# 4_SFP.net
KiCad netlist of a schematic drawn in Altium Designer
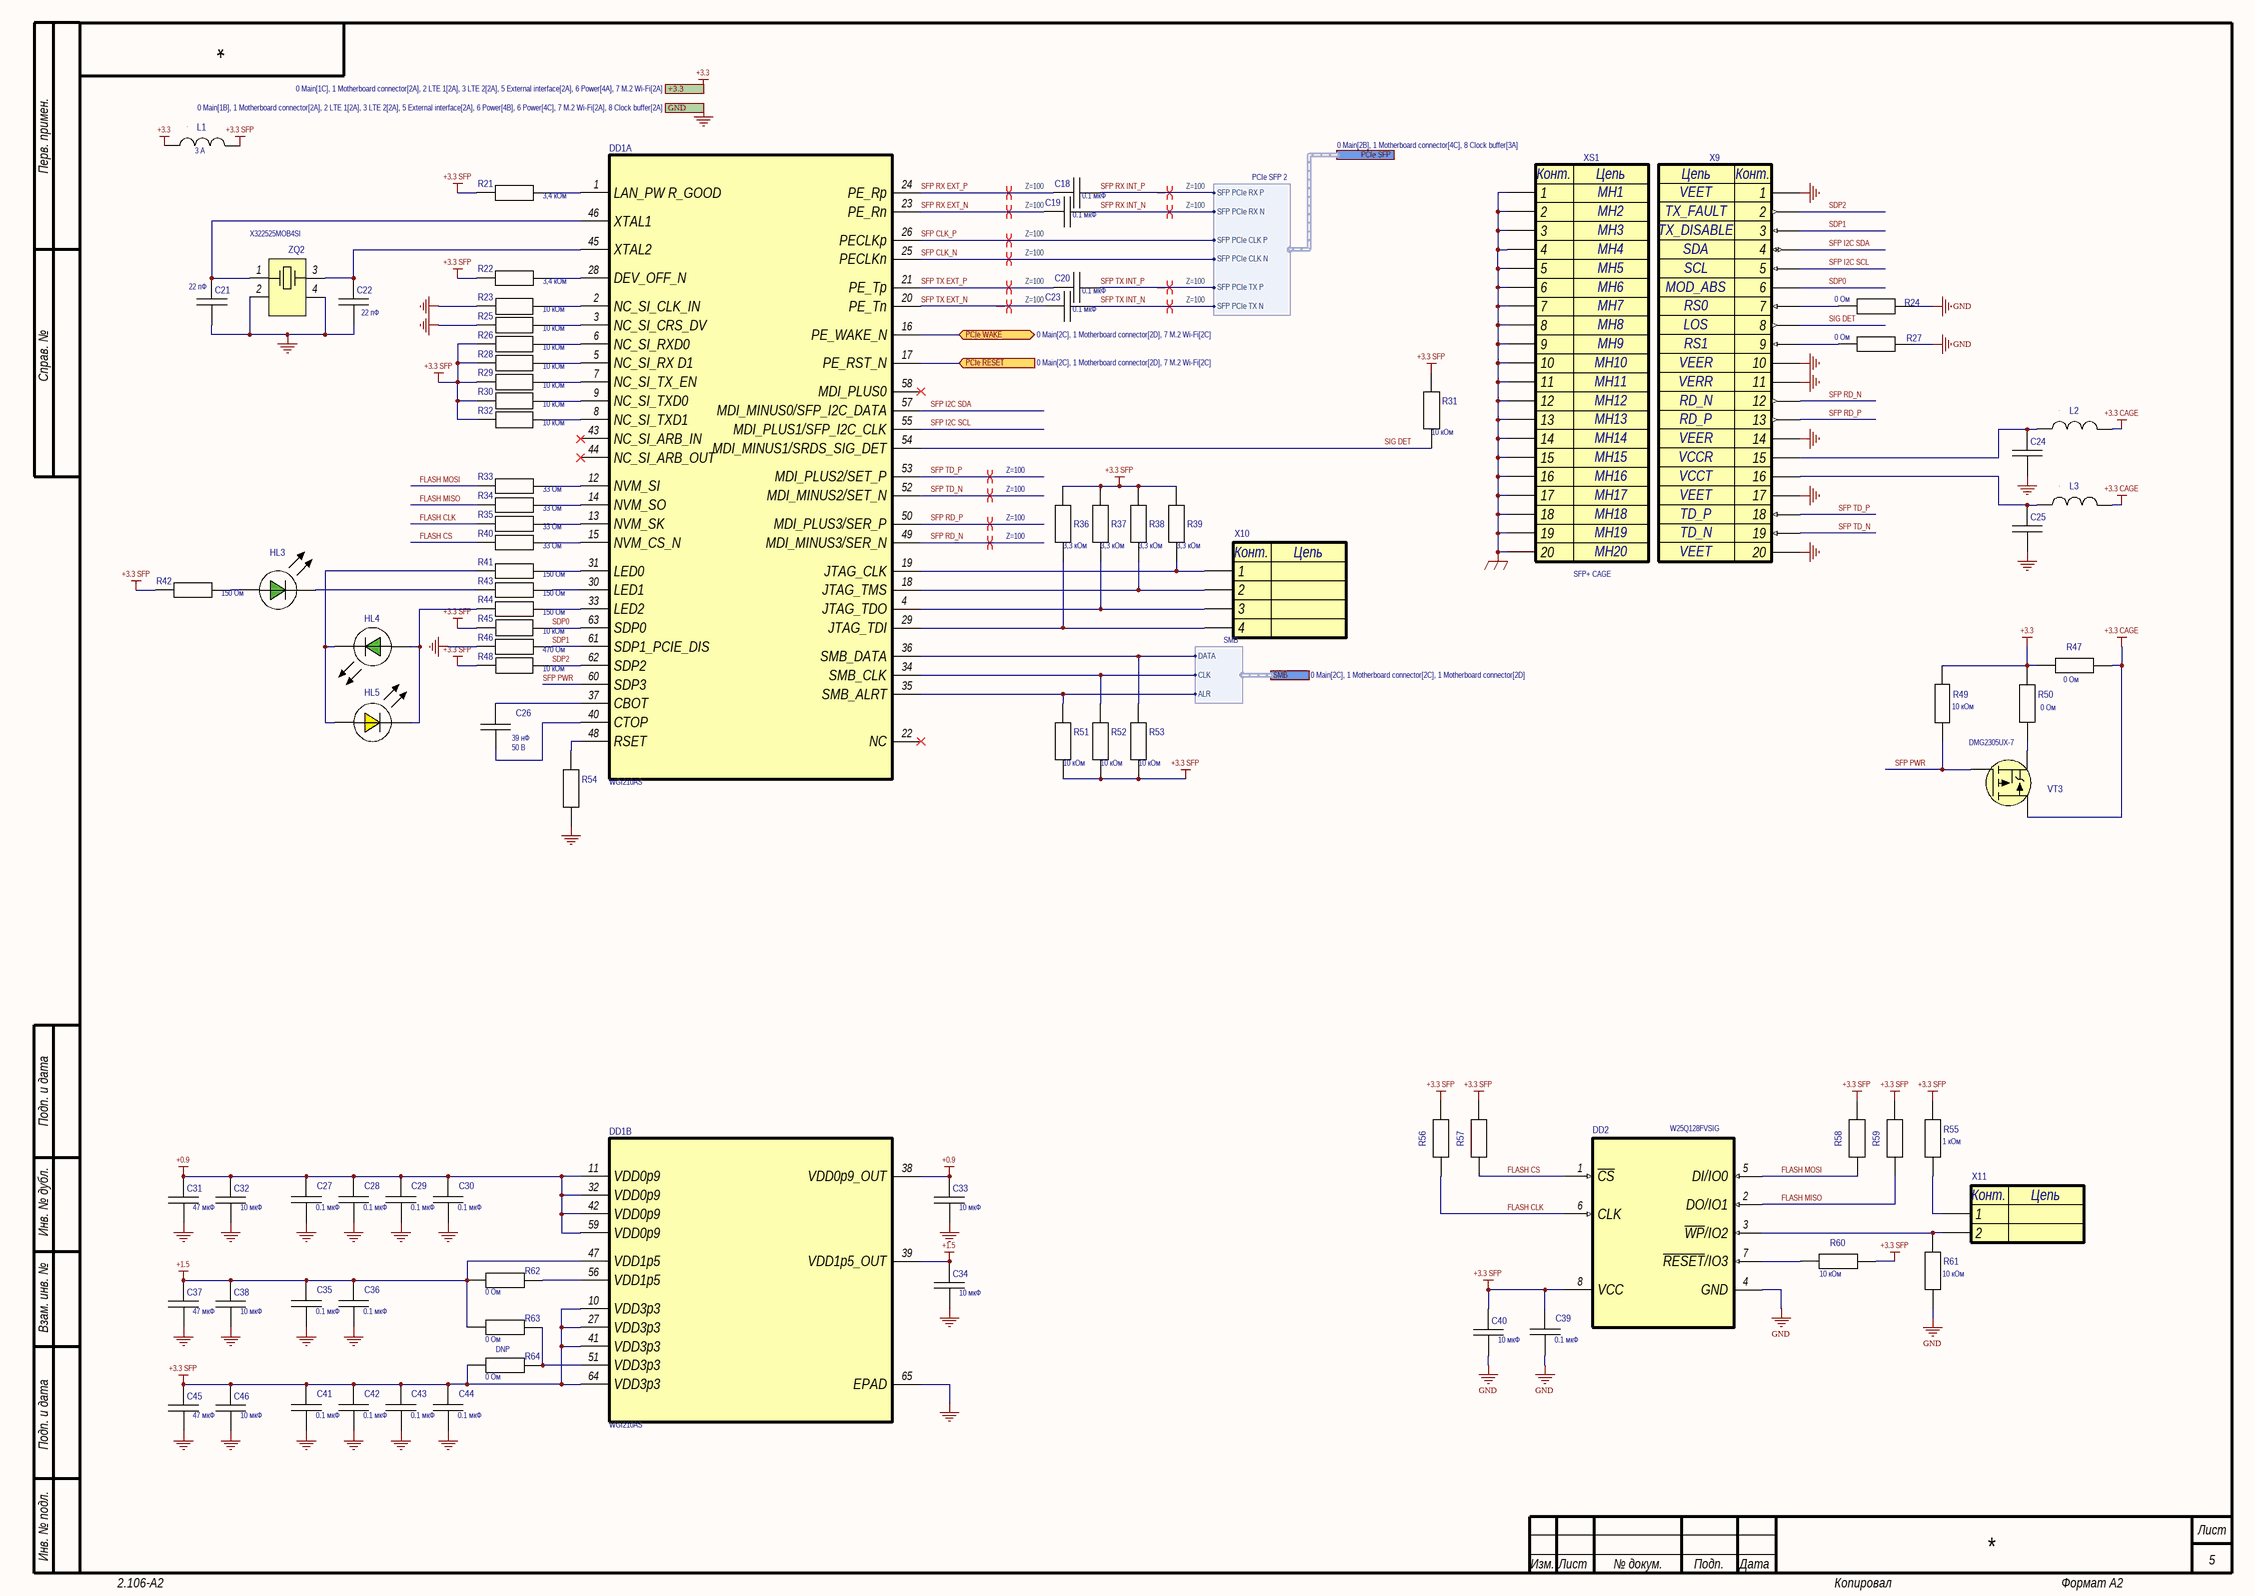
[diagram p0: 4 SFP.SchDoc]

(export (version "E")
  (design (tool "Eeschema 10.0.6"))
  (components
    (comp (ref "C18")
      (value "0.1 мкФ")
      (footprint "CAP_0402")
      (description "Конденсатор CHIP-0402 0.1 мкФ 50 В 10% X7R")
      (fields (field (name "PARTNUMBER") "CC0402KRX7R9BB104") (field (name "TOLERANCE") "10%"))
      (libsource (lib "Database_Altium") (part "STD_CAP"))
    )
    (comp (ref "C19")
      (value "0.1 мкФ")
      (footprint "CAP_0402")
      (description "Конденсатор CHIP-0402 0.1 мкФ 50 В 10% X7R")
      (fields (field (name "PARTNUMBER") "CC0402KRX7R9BB104") (field (name "TOLERANCE") "10%"))
      (libsource (lib "Database_Altium") (part "STD_CAP"))
    )
    (comp (ref "C20")
      (value "0.1 мкФ")
      (footprint "CAP_0402")
      (description "Конденсатор CHIP-0402 0.1 мкФ 50 В 10% X7R")
      (fields (field (name "PARTNUMBER") "CC0402KRX7R9BB104") (field (name "TOLERANCE") "10%"))
      (libsource (lib "Database_Altium") (part "STD_CAP"))
    )
    (comp (ref "C21")
      (value "22 пФ")
      (footprint "CAP_0402")
      (description "Конденсатор CHIP-0402 22 пФ 50 В 5% NPO")
      (fields (field (name "PARTNUMBER") "CC0402JRNPO9BN220") (field (name "TOLERANCE") "5%"))
      (libsource (lib "Database_Altium") (part "STD_CAP"))
    )
    (comp (ref "C22")
      (value "22 пФ")
      (footprint "CAP_0402")
      (description "Конденсатор CHIP-0402 22 пФ 50 В 5% NPO")
      (fields (field (name "PARTNUMBER") "CC0402JRNPO9BN220") (field (name "TOLERANCE") "5%"))
      (libsource (lib "Database_Altium") (part "STD_CAP"))
    )
    (comp (ref "C23")
      (value "0.1 мкФ")
      (footprint "CAP_0402")
      (description "Конденсатор CHIP-0402 0.1 мкФ 50 В 10% X7R")
      (fields (field (name "PARTNUMBER") "CC0402KRX7R9BB104") (field (name "TOLERANCE") "10%"))
      (libsource (lib "Database_Altium") (part "STD_CAP"))
    )
    (comp (ref "C24")
      (value "~")
      (footprint "CAP_0805")
      (description "Конденсатор CHIP-0805 4.7 мкФ 10 В 10% X7R")
      (fields (field (name "PARTNUMBER") "CC0805KKX7R6BB475") (field (name "TOLERANCE") "10%"))
      (libsource (lib "Database_Altium") (part "STD_CAP"))
    )
    (comp (ref "C25")
      (value "~")
      (footprint "CAP_0805")
      (description "Конденсатор CHIP-0805 4.7 мкФ 10 В 10% X7R")
      (fields (field (name "PARTNUMBER") "CC0805KKX7R6BB475") (field (name "TOLERANCE") "10%"))
      (libsource (lib "Database_Altium") (part "STD_CAP"))
    )
    (comp (ref "C26")
      (value "39 нФ")
      (footprint "CAP_0603")
      (description "Конденсатор CHIP-0603 39 нФ 50 В 10% X7R")
      (fields
        (field (name "PARTNUMBER") "CC0603KRX7R9BB393")
        (field (name "TOLERANCE") "10%")
        (field (name "НАПРЯЖЕНИЕ") "50 В")
      )
      (libsource (lib "Database_Altium") (part "STD_CAP"))
    )
    (comp (ref "C27")
      (value "0.1 мкФ")
      (footprint "CAP_0402")
      (description "Конденсатор CHIP-0402 0.1 мкФ 50 В 10% X7R")
      (fields (field (name "PARTNUMBER") "CC0402KRX7R9BB104") (field (name "TOLERANCE") "10%"))
      (libsource (lib "Database_Altium") (part "STD_CAP"))
    )
    (comp (ref "C28")
      (value "0.1 мкФ")
      (footprint "CAP_0402")
      (description "Конденсатор CHIP-0402 0.1 мкФ 50 В 10% X7R")
      (fields (field (name "PARTNUMBER") "CC0402KRX7R9BB104") (field (name "TOLERANCE") "10%"))
      (libsource (lib "Database_Altium") (part "STD_CAP"))
    )
    (comp (ref "C29")
      (value "0.1 мкФ")
      (footprint "CAP_0402")
      (description "Конденсатор CHIP-0402 0.1 мкФ 50 В 10% X7R")
      (fields (field (name "PARTNUMBER") "CC0402KRX7R9BB104") (field (name "TOLERANCE") "10%"))
      (libsource (lib "Database_Altium") (part "STD_CAP"))
    )
    (comp (ref "C30")
      (value "0.1 мкФ")
      (footprint "CAP_0402")
      (description "Конденсатор CHIP-0402 0.1 мкФ 50 В 10% X7R")
      (fields (field (name "PARTNUMBER") "CC0402KRX7R9BB104") (field (name "TOLERANCE") "10%"))
      (libsource (lib "Database_Altium") (part "STD_CAP"))
    )
    (comp (ref "C31")
      (value "47 мкФ")
      (footprint "CAP_0805")
      (description "Конденсатор CHIP-0805 47 мкФ 6.3 В 20% X5R")
      (fields (field (name "PARTNUMBER") "GRM21BR60J476ME15L") (field (name "TOLERANCE") "20%"))
      (libsource (lib "Database_Altium") (part "STD_CAP"))
    )
    (comp (ref "C32")
      (value "10 мкФ")
      (footprint "CAP_0402_BIG")
      (description "Конденсатор CHIP-0402 10 мкФ 6.3 В 20% X5R")
      (fields (field (name "PARTNUMBER") "CC0402MRX5R5BB106") (field (name "TOLERANCE") "20%"))
      (libsource (lib "Database_Altium") (part "STD_CAP"))
    )
    (comp (ref "C33")
      (value "10 мкФ")
      (footprint "CAP_0402_BIG")
      (description "Конденсатор CHIP-0402 10 мкФ 6.3 В 20% X5R")
      (fields (field (name "PARTNUMBER") "CC0402MRX5R5BB106") (field (name "TOLERANCE") "20%"))
      (libsource (lib "Database_Altium") (part "STD_CAP"))
    )
    (comp (ref "C34")
      (value "10 мкФ")
      (footprint "CAP_0402_BIG")
      (description "Конденсатор CHIP-0402 10 мкФ 6.3 В 20% X5R")
      (fields (field (name "PARTNUMBER") "CC0402MRX5R5BB106") (field (name "TOLERANCE") "20%"))
      (libsource (lib "Database_Altium") (part "STD_CAP"))
    )
    (comp (ref "C35")
      (value "0.1 мкФ")
      (footprint "CAP_0402")
      (description "Конденсатор CHIP-0402 0.1 мкФ 50 В 10% X7R")
      (fields (field (name "PARTNUMBER") "CC0402KRX7R9BB104") (field (name "TOLERANCE") "10%"))
      (libsource (lib "Database_Altium") (part "STD_CAP"))
    )
    (comp (ref "C36")
      (value "0.1 мкФ")
      (footprint "CAP_0402")
      (description "Конденсатор CHIP-0402 0.1 мкФ 50 В 10% X7R")
      (fields (field (name "PARTNUMBER") "CC0402KRX7R9BB104") (field (name "TOLERANCE") "10%"))
      (libsource (lib "Database_Altium") (part "STD_CAP"))
    )
    (comp (ref "C37")
      (value "47 мкФ")
      (footprint "CAP_0805")
      (description "Конденсатор CHIP-0805 47 мкФ 6.3 В 20% X5R")
      (fields (field (name "PARTNUMBER") "GRM21BR60J476ME15L") (field (name "TOLERANCE") "20%"))
      (libsource (lib "Database_Altium") (part "STD_CAP"))
    )
    (comp (ref "C38")
      (value "10 мкФ")
      (footprint "CAP_0402_BIG")
      (description "Конденсатор CHIP-0402 10 мкФ 6.3 В 20% X5R")
      (fields (field (name "PARTNUMBER") "CC0402MRX5R5BB106") (field (name "TOLERANCE") "20%"))
      (libsource (lib "Database_Altium") (part "STD_CAP"))
    )
    (comp (ref "C39")
      (value "0.1 мкФ")
      (footprint "CAP_0402")
      (description "Конденсатор CHIP-0402 0.1 мкФ 50 В 10% X7R")
      (fields (field (name "PARTNUMBER") "CC0402KRX7R9BB104") (field (name "TOLERANCE") "10%"))
      (libsource (lib "Database_Altium") (part "STD_CAP"))
    )
    (comp (ref "C40")
      (value "10 мкФ")
      (footprint "CAP_0402_BIG")
      (description "Конденсатор CHIP-0402 10 мкФ 6.3 В 20% X5R")
      (fields (field (name "PARTNUMBER") "CC0402MRX5R5BB106") (field (name "TOLERANCE") "20%"))
      (libsource (lib "Database_Altium") (part "STD_CAP"))
    )
    (comp (ref "C41")
      (value "0.1 мкФ")
      (footprint "CAP_0402")
      (description "Конденсатор CHIP-0402 0.1 мкФ 50 В 10% X7R")
      (fields (field (name "PARTNUMBER") "CC0402KRX7R9BB104") (field (name "TOLERANCE") "10%"))
      (libsource (lib "Database_Altium") (part "STD_CAP"))
    )
    (comp (ref "C42")
      (value "0.1 мкФ")
      (footprint "CAP_0402")
      (description "Конденсатор CHIP-0402 0.1 мкФ 50 В 10% X7R")
      (fields (field (name "PARTNUMBER") "CC0402KRX7R9BB104") (field (name "TOLERANCE") "10%"))
      (libsource (lib "Database_Altium") (part "STD_CAP"))
    )
    (comp (ref "C43")
      (value "0.1 мкФ")
      (footprint "CAP_0402")
      (description "Конденсатор CHIP-0402 0.1 мкФ 50 В 10% X7R")
      (fields (field (name "PARTNUMBER") "CC0402KRX7R9BB104") (field (name "TOLERANCE") "10%"))
      (libsource (lib "Database_Altium") (part "STD_CAP"))
    )
    (comp (ref "C44")
      (value "0.1 мкФ")
      (footprint "CAP_0402")
      (description "Конденсатор CHIP-0402 0.1 мкФ 50 В 10% X7R")
      (fields (field (name "PARTNUMBER") "CC0402KRX7R9BB104") (field (name "TOLERANCE") "10%"))
      (libsource (lib "Database_Altium") (part "STD_CAP"))
    )
    (comp (ref "C45")
      (value "47 мкФ")
      (footprint "CAP_0805")
      (description "Конденсатор CHIP-0805 47 мкФ 6.3 В 20% X5R")
      (fields (field (name "PARTNUMBER") "GRM21BR60J476ME15L") (field (name "TOLERANCE") "20%"))
      (libsource (lib "Database_Altium") (part "STD_CAP"))
    )
    (comp (ref "C46")
      (value "10 мкФ")
      (footprint "CAP_0402_BIG")
      (description "Конденсатор CHIP-0402 10 мкФ 6.3 В 20% X5R")
      (fields (field (name "PARTNUMBER") "CC0402MRX5R5BB106") (field (name "TOLERANCE") "20%"))
      (libsource (lib "Database_Altium") (part "STD_CAP"))
    )
    (comp (ref "DD1")
      (value "WGI210AS")
      (footprint "QFN64-9X9-P05_WGI210AS")
      (description "Микросхема Intel  Ethernet Controller  PCIe v2.1 (2.5 GT/s) x1")
      (fields (field (name "VOLTAGE") "3.3 В") (field (name "MANUFACTURER") "Intel"))
      (libsource (lib "Database_Altium") (part "WGI210AS"))
    )
    (comp (ref "DD2")
      (value "W25Q128FVSIG")
      (footprint "SOIC-8-208mil")
      (description "Микросхема Winbond  3V 128M-BIT\r\nSERIAL FLASH MEMORY WITH\r\nDUAL/QUAD SPI & QPI")
      (fields
        (field (name "PARTNUMBER") "W25Q128FVSIG")
        (field (name "VOLTAGE") "2.7-3.3В")
        (field (name "MANUFACTURER") "Winbond")
      )
      (libsource (lib "Database_Altium") (part "W25Q128FVSIG"))
    )
    (comp (ref "HL3")
      (value "155124GS73200")
      (footprint "LED_1204_GREEN")
      (description "Диод Wurth 2 В 25 мА")
      (fields (field (name "MANUFACTURER") "Wurth"))
      (libsource (lib "Database_Altium") (part "STD_LED_GREEN"))
    )
    (comp (ref "HL4")
      (value "155124GS73200")
      (footprint "LED_1204_GREEN")
      (description "Диод Wurth 2 В 25 мА")
      (fields (field (name "MANUFACTURER") "Wurth"))
      (libsource (lib "Database_Altium") (part "STD_LED_GREEN"))
    )
    (comp (ref "HL5")
      (value "155124YS73200")
      (footprint "LED_1204_YELLOW")
      (description "Диод Wurth 2 В 25 мА")
      (fields (field (name "MANUFACTURER") "Wurth"))
      (libsource (lib "Database_Altium") (part "STD_LED_YELLOW"))
    )
    (comp (ref "L1")
      (value "STD_IND")
      (footprint "IND_0603")
      (description "Катушка индуктивности BEAD-0603 33 Ом @100 МГц 25%")
      (fields
        (field (name "PARTNUMBER") "BLM18PG330SN1D")
        (field (name "TOLERANCE") "25%")
        (field (name "CURRENT") "3 А")
      )
      (libsource (lib "Database_Altium") (part "STD_IND"))
    )
    (comp (ref "L2")
      (value "STD_IND")
      (footprint "IND_0603")
      (description "Катушка индуктивности CHIP-0603 3.3 мкГн 10%")
      (fields (field (name "PARTNUMBER") "MLF1608A3R3KTA00") (field (name "TOLERANCE") "10%"))
      (libsource (lib "Database_Altium") (part "STD_IND"))
    )
    (comp (ref "L3")
      (value "STD_IND")
      (footprint "IND_0603")
      (description "Катушка индуктивности CHIP-0603 3.3 мкГн 10%")
      (fields (field (name "PARTNUMBER") "MLF1608A3R3KTA00") (field (name "TOLERANCE") "10%"))
      (libsource (lib "Database_Altium") (part "STD_IND"))
    )
    (comp (ref "R21")
      (value "3,4 кОм")
      (footprint "RES_0402")
      (description "Резистор CHIP-0402 3,4 кОм 1%")
      (fields (field (name "PARTNUMBER") "RC0402FR-073K4L") (field (name "TOLERANCE") "1%"))
      (libsource (lib "Database_Altium") (part "STD_RES"))
    )
    (comp (ref "R22")
      (value "3,4 кОм")
      (footprint "RES_0402")
      (description "Резистор CHIP-0402 3,4 кОм 1%")
      (fields (field (name "PARTNUMBER") "RC0402FR-073K4L") (field (name "TOLERANCE") "1%"))
      (libsource (lib "Database_Altium") (part "STD_RES"))
    )
    (comp (ref "R23")
      (value "10 кОм")
      (footprint "RES_0402")
      (description "Резистор CHIP-0402 10 кОм 1%")
      (fields (field (name "PARTNUMBER") "RC0402FR-0710KL") (field (name "TOLERANCE") "1%"))
      (libsource (lib "Database_Altium") (part "STD_RES"))
    )
    (comp (ref "R24")
      (value "0 Ом")
      (footprint "RES_0402")
      (description "Резистор CHIP-0402 0 Ом 5%")
      (fields (field (name "PARTNUMBER") "RC0402JR-070RL") (field (name "TOLERANCE") "5%"))
      (libsource (lib "Database_Altium") (part "STD_RES"))
    )
    (comp (ref "R25")
      (value "10 кОм")
      (footprint "RES_0402")
      (description "Резистор CHIP-0402 10 кОм 1%")
      (fields (field (name "PARTNUMBER") "RC0402FR-0710KL") (field (name "TOLERANCE") "1%"))
      (libsource (lib "Database_Altium") (part "STD_RES"))
    )
    (comp (ref "R26")
      (value "10 кОм")
      (footprint "RES_0402")
      (description "Резистор CHIP-0402 10 кОм 1%")
      (fields (field (name "PARTNUMBER") "RC0402FR-0710KL") (field (name "TOLERANCE") "1%"))
      (libsource (lib "Database_Altium") (part "STD_RES"))
    )
    (comp (ref "R27")
      (value "0 Ом")
      (footprint "RES_0402")
      (description "Резистор CHIP-0402 0 Ом 5%")
      (fields (field (name "PARTNUMBER") "RC0402JR-070RL") (field (name "TOLERANCE") "5%"))
      (libsource (lib "Database_Altium") (part "STD_RES"))
    )
    (comp (ref "R28")
      (value "10 кОм")
      (footprint "RES_0402")
      (description "Резистор CHIP-0402 10 кОм 1%")
      (fields (field (name "PARTNUMBER") "RC0402FR-0710KL") (field (name "TOLERANCE") "1%"))
      (libsource (lib "Database_Altium") (part "STD_RES"))
    )
    (comp (ref "R29")
      (value "10 кОм")
      (footprint "RES_0402")
      (description "Резистор CHIP-0402 10 кОм 1%")
      (fields (field (name "PARTNUMBER") "RC0402FR-0710KL") (field (name "TOLERANCE") "1%"))
      (libsource (lib "Database_Altium") (part "STD_RES"))
    )
    (comp (ref "R30")
      (value "10 кОм")
      (footprint "RES_0402")
      (description "Резистор CHIP-0402 10 кОм 1%")
      (fields (field (name "PARTNUMBER") "RC0402FR-0710KL") (field (name "TOLERANCE") "1%"))
      (libsource (lib "Database_Altium") (part "STD_RES"))
    )
    (comp (ref "R31")
      (value "10 кОм")
      (footprint "RES_0402")
      (description "Резистор CHIP-0402 10 кОм 5%")
      (fields (field (name "PARTNUMBER") "RC0402JR-0710KL") (field (name "TOLERANCE") "5%"))
      (libsource (lib "Database_Altium") (part "STD_RES"))
    )
    (comp (ref "R32")
      (value "10 кОм")
      (footprint "RES_0402")
      (description "Резистор CHIP-0402 10 кОм 1%")
      (fields (field (name "PARTNUMBER") "RC0402FR-0710KL") (field (name "TOLERANCE") "1%"))
      (libsource (lib "Database_Altium") (part "STD_RES"))
    )
    (comp (ref "R33")
      (value "33 Ом")
      (footprint "RES_0402")
      (description "Резистор CHIP-0402 33 Ом 1%")
      (fields (field (name "PARTNUMBER") "RC0402FR-0733RL") (field (name "TOLERANCE") "1%"))
      (libsource (lib "Database_Altium") (part "STD_RES"))
    )
    (comp (ref "R34")
      (value "33 Ом")
      (footprint "RES_0402")
      (description "Резистор CHIP-0402 33 Ом 1%")
      (fields (field (name "PARTNUMBER") "RC0402FR-0733RL") (field (name "TOLERANCE") "1%"))
      (libsource (lib "Database_Altium") (part "STD_RES"))
    )
    (comp (ref "R35")
      (value "33 Ом")
      (footprint "RES_0402")
      (description "Резистор CHIP-0402 33 Ом 1%")
      (fields (field (name "PARTNUMBER") "RC0402FR-0733RL") (field (name "TOLERANCE") "1%"))
      (libsource (lib "Database_Altium") (part "STD_RES"))
    )
    (comp (ref "R36")
      (value "3,3 кОм")
      (footprint "RES_0402")
      (description "Резистор CHIP-0402 3,3 кОм 5%")
      (fields (field (name "PARTNUMBER") "RC0402JR-073K3L") (field (name "TOLERANCE") "5%"))
      (libsource (lib "Database_Altium") (part "STD_RES"))
    )
    (comp (ref "R37")
      (value "3,3 кОм")
      (footprint "RES_0402")
      (description "Резистор CHIP-0402 3,3 кОм 5%")
      (fields (field (name "PARTNUMBER") "RC0402JR-073K3L") (field (name "TOLERANCE") "5%"))
      (libsource (lib "Database_Altium") (part "STD_RES"))
    )
    (comp (ref "R38")
      (value "3,3 кОм")
      (footprint "RES_0402")
      (description "Резистор CHIP-0402 3,3 кОм 5%")
      (fields (field (name "PARTNUMBER") "RC0402JR-073K3L") (field (name "TOLERANCE") "5%"))
      (libsource (lib "Database_Altium") (part "STD_RES"))
    )
    (comp (ref "R39")
      (value "3,3 кОм")
      (footprint "RES_0402")
      (description "Резистор CHIP-0402 3,3 кОм 5%")
      (fields (field (name "PARTNUMBER") "RC0402JR-073K3L") (field (name "TOLERANCE") "5%"))
      (libsource (lib "Database_Altium") (part "STD_RES"))
    )
    (comp (ref "R40")
      (value "33 Ом")
      (footprint "RES_0402")
      (description "Резистор CHIP-0402 33 Ом 1%")
      (fields (field (name "PARTNUMBER") "RC0402FR-0733RL") (field (name "TOLERANCE") "1%"))
      (libsource (lib "Database_Altium") (part "STD_RES"))
    )
    (comp (ref "R41")
      (value "150 Ом")
      (footprint "RES_0402")
      (description "Резистор CHIP-0402 150 Ом 5%")
      (fields (field (name "PARTNUMBER") "RC0402JR-07150RL") (field (name "TOLERANCE") "5%"))
      (libsource (lib "Database_Altium") (part "STD_RES"))
    )
    (comp (ref "R42")
      (value "150 Ом")
      (footprint "RES_0402")
      (description "Резистор CHIP-0402 150 Ом 5%")
      (fields (field (name "PARTNUMBER") "RC0402JR-07150RL") (field (name "TOLERANCE") "5%"))
      (libsource (lib "Database_Altium") (part "STD_RES"))
    )
    (comp (ref "R43")
      (value "150 Ом")
      (footprint "RES_0402")
      (description "Резистор CHIP-0402 150 Ом 5%")
      (fields (field (name "PARTNUMBER") "RC0402JR-07150RL") (field (name "TOLERANCE") "5%"))
      (libsource (lib "Database_Altium") (part "STD_RES"))
    )
    (comp (ref "R44")
      (value "150 Ом")
      (footprint "RES_0402")
      (description "Резистор CHIP-0402 150 Ом 5%")
      (fields (field (name "PARTNUMBER") "RC0402JR-07150RL") (field (name "TOLERANCE") "5%"))
      (libsource (lib "Database_Altium") (part "STD_RES"))
    )
    (comp (ref "R45")
      (value "10 кОм")
      (footprint "RES_0402")
      (description "Резистор CHIP-0402 10 кОм 1%")
      (fields (field (name "PARTNUMBER") "RC0402FR-0710KL") (field (name "TOLERANCE") "1%"))
      (libsource (lib "Database_Altium") (part "STD_RES"))
    )
    (comp (ref "R46")
      (value "470 Ом")
      (footprint "RES_0402")
      (description "Резистор CHIP-0402 470 Ом 5%")
      (fields (field (name "PARTNUMBER") "RC0402JR-07470RL") (field (name "TOLERANCE") "5%"))
      (libsource (lib "Database_Altium") (part "STD_RES"))
    )
    (comp (ref "R47")
      (value "0 Ом")
      (footprint "RES_1206")
      (description "Резистор CHIP-1206 0 Ом 5%")
      (fields (field (name "PARTNUMBER") "RC1206JR-070RL") (field (name "TOLERANCE") "5%"))
      (libsource (lib "Database_Altium") (part "STD_RES"))
    )
    (comp (ref "R48")
      (value "10 кОм")
      (footprint "RES_0402")
      (description "Резистор CHIP-0402 10 кОм 1%")
      (fields (field (name "PARTNUMBER") "RC0402FR-0710KL") (field (name "TOLERANCE") "1%"))
      (libsource (lib "Database_Altium") (part "STD_RES"))
    )
    (comp (ref "R49")
      (value "10 кОм")
      (footprint "RES_0402")
      (description "Резистор CHIP-0402 10 кОм 1%")
      (fields (field (name "PARTNUMBER") "RC0402FR-0710KL") (field (name "TOLERANCE") "1%"))
      (libsource (lib "Database_Altium") (part "STD_RES"))
    )
    (comp (ref "R50")
      (value "0 Ом")
      (footprint "RES_1206")
      (description "Резистор CHIP-1206 0 Ом 5%")
      (fields (field (name "PARTNUMBER") "RC1206JR-070RL") (field (name "TOLERANCE") "5%"))
      (libsource (lib "Database_Altium") (part "STD_RES"))
    )
    (comp (ref "R51")
      (value "10 кОм")
      (footprint "RES_0402")
      (description "Резистор CHIP-0402 10 кОм 5%")
      (fields (field (name "PARTNUMBER") "RC0402JR-0710KL") (field (name "TOLERANCE") "5%"))
      (libsource (lib "Database_Altium") (part "STD_RES"))
    )
    (comp (ref "R52")
      (value "10 кОм")
      (footprint "RES_0402")
      (description "Резистор CHIP-0402 10 кОм 5%")
      (fields (field (name "PARTNUMBER") "RC0402JR-0710KL") (field (name "TOLERANCE") "5%"))
      (libsource (lib "Database_Altium") (part "STD_RES"))
    )
    (comp (ref "R53")
      (value "10 кОм")
      (footprint "RES_0402")
      (description "Резистор CHIP-0402 10 кОм 5%")
      (fields (field (name "PARTNUMBER") "RC0402JR-0710KL") (field (name "TOLERANCE") "5%"))
      (libsource (lib "Database_Altium") (part "STD_RES"))
    )
    (comp (ref "R54")
      (value "STD_RES")
      (footprint "RES_0402")
      (description "Резистор CHIP-0402 4,7 кОм 5%")
      (fields (field (name "PARTNUMBER") "RC0402JR-074K7L") (field (name "TOLERANCE") "5%"))
      (libsource (lib "Database_Altium") (part "STD_RES"))
    )
    (comp (ref "R55")
      (value "1 кОм")
      (footprint "RES_0805")
      (description "Резистор CHIP-0805 1 кОм 5%")
      (fields (field (name "PARTNUMBER") "RC0805JR-071KL") (field (name "TOLERANCE") "5%"))
      (libsource (lib "Database_Altium") (part "STD_RES"))
    )
    (comp (ref "R56")
      (value "STD_RES")
      (footprint "RES_0402")
      (description "Резистор CHIP-0402 4,7 кОм 5%")
      (fields (field (name "PARTNUMBER") "RC0402JR-074K7L") (field (name "TOLERANCE") "5%"))
      (libsource (lib "Database_Altium") (part "STD_RES"))
    )
    (comp (ref "R57")
      (value "STD_RES")
      (footprint "RES_0402")
      (description "Резистор CHIP-0402 4,7 кОм 5%")
      (fields (field (name "PARTNUMBER") "RC0402JR-074K7L") (field (name "TOLERANCE") "5%"))
      (libsource (lib "Database_Altium") (part "STD_RES"))
    )
    (comp (ref "R58")
      (value "STD_RES")
      (footprint "RES_0402")
      (description "Резистор CHIP-0402 4,7 кОм 5%")
      (fields (field (name "PARTNUMBER") "RC0402JR-074K7L") (field (name "TOLERANCE") "5%"))
      (libsource (lib "Database_Altium") (part "STD_RES"))
    )
    (comp (ref "R59")
      (value "STD_RES")
      (footprint "RES_0402")
      (description "Резистор CHIP-0402 4,7 кОм 5%")
      (fields (field (name "PARTNUMBER") "RC0402JR-074K7L") (field (name "TOLERANCE") "5%"))
      (libsource (lib "Database_Altium") (part "STD_RES"))
    )
    (comp (ref "R60")
      (value "10 кОм")
      (footprint "RES_0402")
      (description "Резистор CHIP-0402 10 кОм 5%")
      (fields (field (name "PARTNUMBER") "RC0402JR-0710KL") (field (name "TOLERANCE") "5%"))
      (libsource (lib "Database_Altium") (part "STD_RES"))
    )
    (comp (ref "R61")
      (value "10 кОм")
      (footprint "RES_0402")
      (description "Резистор CHIP-0402 10 кОм 5%")
      (fields (field (name "PARTNUMBER") "RC0402JR-0710KL") (field (name "TOLERANCE") "5%"))
      (libsource (lib "Database_Altium") (part "STD_RES"))
    )
    (comp (ref "R62")
      (value "0 Ом")
      (footprint "RES_0402")
      (description "Резистор CHIP-0402 0 Ом 5%")
      (fields (field (name "PARTNUMBER") "RC0402JR-070RL") (field (name "TOLERANCE") "5%"))
      (libsource (lib "Database_Altium") (part "STD_RES"))
    )
    (comp (ref "R63")
      (value "0 Ом")
      (footprint "RES_0402")
      (description "Резистор CHIP-0402 0 Ом 5%")
      (fields (field (name "PARTNUMBER") "RC0402JR-070RL") (field (name "TOLERANCE") "5%"))
      (libsource (lib "Database_Altium") (part "STD_RES"))
    )
    (comp (ref "R64")
      (value "0 Ом")
      (footprint "RES_0402")
      (description "Резистор CHIP-0402 0 Ом 5%")
      (fields (field (name "PARTNUMBER") "RC0402JR-070RL") (field (name "TOLERANCE") "5%"))
      (libsource (lib "Database_Altium") (part "STD_RES"))
    )
    (comp (ref "VT3")
      (value "DMG2305UX-7")
      (footprint "SOT-23-3")
      (description "Микросхема Diode Inc MOSFET P-Channel 20V 4.2A")
      (fields
        (field (name "PARTNUMBER") "DMG2305UX-7")
        (field (name "VOLTAGE") "20 В")
        (field (name "MANUFACTURER") "Diode Inc")
      )
      (libsource (lib "Database_Altium") (part "DMG2305UX-7"))
    )
    (comp (ref "X9")
      (value "Разъем оптический")
      (footprint "1888247-1")
      (description "Разъем TE SFP")
      (fields (field (name "PARTNUMBER") "1888247-1") (field (name "MANUFACTURER") "TE"))
      (libsource (lib "Database_Altium") (part "1888247-1"))
    )
    (comp (ref "X10")
      (value "STD_CON4")
      (footprint "PLS-4")
      (description "Разъем Connfly PLS")
      (fields (field (name "PARTNUMBER") "DS1021-1x4SF11-B (PLS-4)") (field (name "MANUFACTURER") "Connfly"))
      (libsource (lib "Database_Altium") (part "STD_CON4"))
    )
    (comp (ref "X11")
      (value "STD_CON2")
      (footprint "PLS-2")
      (description "Разъем NoName PLS")
      (fields (field (name "PARTNUMBER") "PLS-2") (field (name "MANUFACTURER") "NoName"))
      (libsource (lib "Database_Altium") (part "STD_CON2"))
    )
    (comp (ref "XS1")
      (value "SFP+ CAGE")
      (footprint "2007198-1")
      (description "Разъем TE SFP")
      (fields (field (name "PARTNUMBER") "2007198-1") (field (name "MANUFACTURER") "TE"))
      (libsource (lib "Database_Altium") (part "2007198-1"))
    )
    (comp (ref "ZQ2")
      (value "X322525MOB4SI")
      (footprint "3.2x2.5_4pin")
      (description "Микросхема YXC  Quartz Cristal 25 MHz ±20ppm")
      (fields (field (name "PARTNUMBER") "X322525MOB4SI") (field (name "MANUFACTURER") "YXC"))
      (libsource (lib "Database_Altium") (part "Quartz 3225"))
    )
  )
  (nets
    (net (code "5") (name "+0.9") (class "Default")
      (node (ref "C27") (pin "2") (pinfunction "2_2") (pintype "passive"))
      (node (ref "C28") (pin "2") (pinfunction "2_2") (pintype "passive"))
      (node (ref "C29") (pin "2") (pinfunction "2_2") (pintype "passive"))
      (node (ref "C30") (pin "2") (pinfunction "2_2") (pintype "passive"))
      (node (ref "C31") (pin "1") (pinfunction "1_1") (pintype "passive"))
      (node (ref "C32") (pin "1") (pinfunction "1_1") (pintype "passive"))
      (node (ref "C33") (pin "1") (pinfunction "1_1") (pintype "passive"))
      (node (ref "DD1") (pin "11") (pinfunction "VDD0p9_11") (pintype "passive"))
      (node (ref "DD1") (pin "32") (pinfunction "VDD0p9_32") (pintype "passive"))
      (node (ref "DD1") (pin "38") (pinfunction "VDD0p9_OUT_38") (pintype "passive"))
      (node (ref "DD1") (pin "42") (pinfunction "VDD0p9_42") (pintype "passive"))
      (node (ref "DD1") (pin "59") (pinfunction "VDD0p9_59") (pintype "passive"))
    )
    (net (code "6") (name "+1.5") (class "Default")
      (node (ref "C34") (pin "1") (pinfunction "1_1") (pintype "passive"))
      (node (ref "C35") (pin "2") (pinfunction "2_2") (pintype "passive"))
      (node (ref "C36") (pin "2") (pinfunction "2_2") (pintype "passive"))
      (node (ref "C37") (pin "1") (pinfunction "1_1") (pintype "passive"))
      (node (ref "C38") (pin "1") (pinfunction "1_1") (pintype "passive"))
      (node (ref "DD1") (pin "39") (pinfunction "VDD1p5_OUT_39") (pintype "passive"))
      (node (ref "DD1") (pin "47") (pinfunction "VDD1p5_47") (pintype "passive"))
      (node (ref "R62") (pin "1") (pinfunction "1_1") (pintype "passive"))
      (node (ref "R63") (pin "1") (pinfunction "1_1") (pintype "passive"))
    )
    (net (code "7") (name "+3.3") (class "Default")
      (node (ref "L1") (pin "1") (pinfunction "1_1") (pintype "passive"))
      (node (ref "R47") (pin "1") (pinfunction "1_1") (pintype "passive"))
      (node (ref "R49") (pin "2") (pinfunction "2_2") (pintype "passive"))
      (node (ref "R50") (pin "2") (pinfunction "2_2") (pintype "passive"))
    )
    (net (code "8") (name "+3.3 CAGE") (class "Default")
      (node (ref "L2") (pin "2") (pinfunction "2_2") (pintype "passive"))
      (node (ref "L3") (pin "2") (pinfunction "2_2") (pintype "passive"))
      (node (ref "R47") (pin "2") (pinfunction "2_2") (pintype "passive"))
      (node (ref "VT3") (pin "3") (pinfunction "D_3") (pintype "passive"))
    )
    (net (code "9") (name "+3.3 SFP") (class "Default")
      (node (ref "C39") (pin "2") (pinfunction "2_2") (pintype "passive"))
      (node (ref "C40") (pin "1") (pinfunction "1_1") (pintype "passive"))
      (node (ref "C41") (pin "2") (pinfunction "2_2") (pintype "passive"))
      (node (ref "C42") (pin "2") (pinfunction "2_2") (pintype "passive"))
      (node (ref "C43") (pin "2") (pinfunction "2_2") (pintype "passive"))
      (node (ref "C44") (pin "2") (pinfunction "2_2") (pintype "passive"))
      (node (ref "C45") (pin "1") (pinfunction "1_1") (pintype "passive"))
      (node (ref "C46") (pin "1") (pinfunction "1_1") (pintype "passive"))
      (node (ref "DD1") (pin "10") (pinfunction "VDD3p3_10") (pintype "power_in"))
      (node (ref "DD1") (pin "27") (pinfunction "VDD3p3_27") (pintype "passive"))
      (node (ref "DD1") (pin "41") (pinfunction "VDD3p3_41") (pintype "passive"))
      (node (ref "DD1") (pin "64") (pinfunction "VDD3p3_64") (pintype "passive"))
      (node (ref "DD2") (pin "8") (pinfunction "VCC_8") (pintype "power_in"))
      (node (ref "L1") (pin "2") (pinfunction "2_2") (pintype "passive"))
      (node (ref "R21") (pin "1") (pinfunction "1_1") (pintype "passive"))
      (node (ref "R22") (pin "2") (pinfunction "2_2") (pintype "passive"))
      (node (ref "R26") (pin "1") (pinfunction "1_1") (pintype "passive"))
      (node (ref "R28") (pin "1") (pinfunction "1_1") (pintype "passive"))
      (node (ref "R29") (pin "1") (pinfunction "1_1") (pintype "passive"))
      (node (ref "R30") (pin "1") (pinfunction "1_1") (pintype "passive"))
      (node (ref "R31") (pin "2") (pinfunction "2_2") (pintype "passive"))
      (node (ref "R32") (pin "1") (pinfunction "1_1") (pintype "passive"))
      (node (ref "R36") (pin "2") (pinfunction "2_2") (pintype "passive"))
      (node (ref "R37") (pin "2") (pinfunction "2_2") (pintype "passive"))
      (node (ref "R38") (pin "2") (pinfunction "2_2") (pintype "passive"))
      (node (ref "R39") (pin "2") (pinfunction "2_2") (pintype "passive"))
      (node (ref "R42") (pin "2") (pinfunction "2_2") (pintype "passive"))
      (node (ref "R45") (pin "1") (pinfunction "1_1") (pintype "passive"))
      (node (ref "R48") (pin "1") (pinfunction "1_1") (pintype "passive"))
      (node (ref "R51") (pin "1") (pinfunction "1_1") (pintype "passive"))
      (node (ref "R52") (pin "1") (pinfunction "1_1") (pintype "passive"))
      (node (ref "R53") (pin "1") (pinfunction "1_1") (pintype "passive"))
      (node (ref "R55") (pin "2") (pinfunction "2_2") (pintype "passive"))
      (node (ref "R56") (pin "2") (pinfunction "2_2") (pintype "passive"))
      (node (ref "R57") (pin "2") (pinfunction "2_2") (pintype "passive"))
      (node (ref "R58") (pin "2") (pinfunction "2_2") (pintype "passive"))
      (node (ref "R59") (pin "2") (pinfunction "2_2") (pintype "passive"))
      (node (ref "R60") (pin "2") (pinfunction "2_2") (pintype "passive"))
      (node (ref "R64") (pin "1") (pinfunction "1_1") (pintype "passive"))
    )
    (net (code "10") (name "/FLASH CLK") (class "Default")
      (node (ref "DD2") (pin "6") (pinfunction "CLK_6") (pintype "input"))
      (node (ref "R35") (pin "1") (pinfunction "1_1") (pintype "passive"))
      (node (ref "R56") (pin "1") (pinfunction "1_1") (pintype "passive"))
    )
    (net (code "11") (name "/FLASH CS") (class "Default")
      (node (ref "DD2") (pin "1") (pinfunction "~{CS}_1") (pintype "input"))
      (node (ref "R40") (pin "1") (pinfunction "1_1") (pintype "passive"))
      (node (ref "R57") (pin "1") (pinfunction "1_1") (pintype "passive"))
    )
    (net (code "12") (name "/FLASH MISO") (class "Default")
      (node (ref "DD2") (pin "2") (pinfunction "DO/IO1_2") (pintype "input"))
      (node (ref "R34") (pin "1") (pinfunction "1_1") (pintype "passive"))
      (node (ref "R59") (pin "1") (pinfunction "1_1") (pintype "passive"))
    )
    (net (code "13") (name "/FLASH MOSI") (class "Default")
      (node (ref "DD2") (pin "5") (pinfunction "DI/IO0_5") (pintype "input"))
      (node (ref "R33") (pin "1") (pinfunction "1_1") (pintype "passive"))
      (node (ref "R58") (pin "1") (pinfunction "1_1") (pintype "passive"))
    )
    (net (code "14") (name "/PCIe RESET") (class "Default")
      (node (ref "DD1") (pin "17") (pinfunction "PE_RST_N_17") (pintype "input"))
    )
    (net (code "15") (name "/PCIe WAKE") (class "Default")
      (node (ref "DD1") (pin "16") (pinfunction "PE_WAKE_N_16") (pintype "bidirectional"))
    )
    (net (code "16") (name "/SDP0") (class "Default")
      (node (ref "DD1") (pin "63") (pinfunction "SDP0_63") (pintype "bidirectional"))
      (node (ref "R45") (pin "2") (pinfunction "2_2") (pintype "passive"))
      (node (ref "X9") (pin "6") (pinfunction "6_6") (pintype "open_collector"))
    )
    (net (code "17") (name "/SDP1") (class "Default")
      (node (ref "DD1") (pin "61") (pinfunction "SDP1_PCIE_DIS_61") (pintype "bidirectional"))
      (node (ref "R46") (pin "2") (pinfunction "2_2") (pintype "passive"))
      (node (ref "X9") (pin "3") (pinfunction "3_3") (pintype "input"))
    )
    (net (code "18") (name "/SDP2") (class "Default")
      (node (ref "DD1") (pin "62") (pinfunction "SDP2_62") (pintype "bidirectional"))
      (node (ref "R48") (pin "2") (pinfunction "2_2") (pintype "passive"))
      (node (ref "X9") (pin "2") (pinfunction "2_2") (pintype "output"))
    )
    (net (code "19") (name "/SFP CLK_N") (class "Default")
      (node (ref "DD1") (pin "25") (pinfunction "PECLKn_25") (pintype "input"))
    )
    (net (code "20") (name "/SFP CLK_P") (class "Default")
      (node (ref "DD1") (pin "26") (pinfunction "PECLKp_26") (pintype "input"))
    )
    (net (code "21") (name "/SFP I2C SCL") (class "Default")
      (node (ref "DD1") (pin "55") (pinfunction "MDI_PLUS1/SFP_I2C_CLK_55") (pintype "bidirectional"))
      (node (ref "X9") (pin "5") (pinfunction "5_5") (pintype "input"))
    )
    (net (code "22") (name "/SFP I2C SDA") (class "Default")
      (node (ref "DD1") (pin "57") (pinfunction "MDI_MINUS0/SFP_I2C_DATA_57") (pintype "bidirectional"))
      (node (ref "X9") (pin "4") (pinfunction "4_4") (pintype "bidirectional"))
    )
    (net (code "23") (name "/SFP PWR") (class "Default")
      (node (ref "DD1") (pin "60") (pinfunction "SDP3_60") (pintype "bidirectional"))
      (node (ref "R49") (pin "1") (pinfunction "1_1") (pintype "passive"))
      (node (ref "VT3") (pin "1") (pinfunction "G_1") (pintype "passive"))
    )
    (net (code "24") (name "/SFP RD_N") (class "Default")
      (node (ref "DD1") (pin "49") (pinfunction "MDI_MINUS3/SER_N_49") (pintype "bidirectional"))
      (node (ref "X9") (pin "12") (pinfunction "12_12") (pintype "output"))
    )
    (net (code "25") (name "/SFP RD_P") (class "Default")
      (node (ref "DD1") (pin "50") (pinfunction "MDI_PLUS3/SER_P_50") (pintype "bidirectional"))
      (node (ref "X9") (pin "13") (pinfunction "13_13") (pintype "output"))
    )
    (net (code "26") (name "/SFP RX EXT_N") (class "Default")
      (node (ref "C19") (pin "1") (pinfunction "1_1") (pintype "passive"))
      (node (ref "DD1") (pin "23") (pinfunction "PE_Rn_23") (pintype "input"))
    )
    (net (code "27") (name "/SFP RX EXT_P") (class "Default")
      (node (ref "C18") (pin "1") (pinfunction "1_1") (pintype "passive"))
      (node (ref "DD1") (pin "24") (pinfunction "PE_Rp_24") (pintype "input"))
    )
    (net (code "28") (name "/SFP RX INT_N") (class "Default")
      (node (ref "C19") (pin "2") (pinfunction "2_2") (pintype "passive"))
    )
    (net (code "29") (name "/SFP RX INT_P") (class "Default")
      (node (ref "C18") (pin "2") (pinfunction "2_2") (pintype "passive"))
    )
    (net (code "30") (name "/SFP TD_N") (class "Default")
      (node (ref "DD1") (pin "52") (pinfunction "MDI_MINUS2/SET_N_52") (pintype "bidirectional"))
      (node (ref "X9") (pin "19") (pinfunction "19_19") (pintype "input"))
    )
    (net (code "31") (name "/SFP TD_P") (class "Default")
      (node (ref "DD1") (pin "53") (pinfunction "MDI_PLUS2/SET_P_53") (pintype "bidirectional"))
      (node (ref "X9") (pin "18") (pinfunction "18_18") (pintype "input"))
    )
    (net (code "32") (name "/SFP TX EXT_N") (class "Default")
      (node (ref "C23") (pin "1") (pinfunction "1_1") (pintype "passive"))
      (node (ref "DD1") (pin "20") (pinfunction "PE_Tn_20") (pintype "output"))
    )
    (net (code "33") (name "/SFP TX EXT_P") (class "Default")
      (node (ref "C20") (pin "1") (pinfunction "1_1") (pintype "passive"))
      (node (ref "DD1") (pin "21") (pinfunction "PE_Tp_21") (pintype "output"))
    )
    (net (code "34") (name "/SFP TX INT_N") (class "Default")
      (node (ref "C23") (pin "2") (pinfunction "2_2") (pintype "passive"))
    )
    (net (code "35") (name "/SFP TX INT_P") (class "Default")
      (node (ref "C20") (pin "2") (pinfunction "2_2") (pintype "passive"))
    )
    (net (code "36") (name "/SIG DET") (class "Default")
      (node (ref "DD1") (pin "54") (pinfunction "MDI_MINUS1/SRDS_SIG_DET_54") (pintype "bidirectional"))
      (node (ref "R31") (pin "1") (pinfunction "1_1") (pintype "passive"))
      (node (ref "X9") (pin "8") (pinfunction "8_8") (pintype "output"))
    )
    (net (code "39") (name "GND") (class "Default")
      (node (ref "C21") (pin "2") (pinfunction "2_2") (pintype "passive"))
      (node (ref "C22") (pin "2") (pinfunction "2_2") (pintype "passive"))
      (node (ref "C24") (pin "2") (pinfunction "2_2") (pintype "passive"))
      (node (ref "C25") (pin "2") (pinfunction "2_2") (pintype "passive"))
      (node (ref "C27") (pin "1") (pinfunction "1_1") (pintype "passive"))
      (node (ref "C28") (pin "1") (pinfunction "1_1") (pintype "passive"))
      (node (ref "C29") (pin "1") (pinfunction "1_1") (pintype "passive"))
      (node (ref "C30") (pin "1") (pinfunction "1_1") (pintype "passive"))
      (node (ref "C31") (pin "2") (pinfunction "2_2") (pintype "passive"))
      (node (ref "C32") (pin "2") (pinfunction "2_2") (pintype "passive"))
      (node (ref "C33") (pin "2") (pinfunction "2_2") (pintype "passive"))
      (node (ref "C34") (pin "2") (pinfunction "2_2") (pintype "passive"))
      (node (ref "C35") (pin "1") (pinfunction "1_1") (pintype "passive"))
      (node (ref "C36") (pin "1") (pinfunction "1_1") (pintype "passive"))
      (node (ref "C37") (pin "2") (pinfunction "2_2") (pintype "passive"))
      (node (ref "C38") (pin "2") (pinfunction "2_2") (pintype "passive"))
      (node (ref "C39") (pin "1") (pinfunction "1_1") (pintype "passive"))
      (node (ref "C40") (pin "2") (pinfunction "2_2") (pintype "passive"))
      (node (ref "C41") (pin "1") (pinfunction "1_1") (pintype "passive"))
      (node (ref "C42") (pin "1") (pinfunction "1_1") (pintype "passive"))
      (node (ref "C43") (pin "1") (pinfunction "1_1") (pintype "passive"))
      (node (ref "C44") (pin "1") (pinfunction "1_1") (pintype "passive"))
      (node (ref "C45") (pin "2") (pinfunction "2_2") (pintype "passive"))
      (node (ref "C46") (pin "2") (pinfunction "2_2") (pintype "passive"))
      (node (ref "DD1") (pin "65") (pinfunction "EPAD_65") (pintype "passive"))
      (node (ref "DD2") (pin "4") (pinfunction "GND_4") (pintype "power_in"))
      (node (ref "R23") (pin "1") (pinfunction "1_1") (pintype "passive"))
      (node (ref "R24") (pin "2") (pinfunction "2_2") (pintype "passive"))
      (node (ref "R25") (pin "1") (pinfunction "1_1") (pintype "passive"))
      (node (ref "R27") (pin "2") (pinfunction "2_2") (pintype "passive"))
      (node (ref "R46") (pin "1") (pinfunction "1_1") (pintype "passive"))
      (node (ref "R54") (pin "1") (pinfunction "1_1") (pintype "passive"))
      (node (ref "R61") (pin "1") (pinfunction "1_1") (pintype "passive"))
      (node (ref "X9") (pin "1") (pinfunction "1_1") (pintype "power_in"))
      (node (ref "X9") (pin "10") (pinfunction "10_10") (pintype "power_in"))
      (node (ref "X9") (pin "11") (pinfunction "11_11") (pintype "power_in"))
      (node (ref "X9") (pin "14") (pinfunction "14_14") (pintype "power_in"))
      (node (ref "X9") (pin "17") (pinfunction "17_17") (pintype "power_in"))
      (node (ref "X9") (pin "20") (pinfunction "20_20") (pintype "power_in"))
      (node (ref "ZQ2") (pin "2") (pinfunction "2_2") (pintype "passive"))
      (node (ref "ZQ2") (pin "4") (pinfunction "4_4") (pintype "passive"))
    )
    (net (code "40") (name "GNDG") (class "Default")
      (node (ref "XS1") (pin "1") (pinfunction "1_1") (pintype "power_in"))
      (node (ref "XS1") (pin "10") (pinfunction "10_10") (pintype "power_in"))
      (node (ref "XS1") (pin "11") (pinfunction "11_11") (pintype "power_in"))
      (node (ref "XS1") (pin "12") (pinfunction "12_12") (pintype "passive"))
      (node (ref "XS1") (pin "13") (pinfunction "13_13") (pintype "passive"))
      (node (ref "XS1") (pin "14") (pinfunction "14_14") (pintype "power_in"))
      (node (ref "XS1") (pin "15") (pinfunction "15_15") (pintype "power_in"))
      (node (ref "XS1") (pin "16") (pinfunction "16_16") (pintype "power_in"))
      (node (ref "XS1") (pin "17") (pinfunction "17_17") (pintype "power_in"))
      (node (ref "XS1") (pin "18") (pinfunction "18_18") (pintype "passive"))
      (node (ref "XS1") (pin "19") (pinfunction "19_19") (pintype "passive"))
      (node (ref "XS1") (pin "2") (pinfunction "2_2") (pintype "passive"))
      (node (ref "XS1") (pin "20") (pinfunction "20_20") (pintype "power_in"))
      (node (ref "XS1") (pin "3") (pinfunction "3_3") (pintype "passive"))
      (node (ref "XS1") (pin "4") (pinfunction "4_4") (pintype "passive"))
      (node (ref "XS1") (pin "5") (pinfunction "5_5") (pintype "passive"))
      (node (ref "XS1") (pin "6") (pinfunction "6_6") (pintype "passive"))
      (node (ref "XS1") (pin "7") (pinfunction "7_7") (pintype "passive"))
      (node (ref "XS1") (pin "8") (pinfunction "8_8") (pintype "passive"))
      (node (ref "XS1") (pin "9") (pinfunction "9_9") (pintype "passive"))
    )
    (net (code "41") (name "Net-(C24-Pad1)") (class "Default")
      (node (ref "C24") (pin "1") (pinfunction "1_1") (pintype "passive"))
      (node (ref "L2") (pin "1") (pinfunction "1_1") (pintype "passive"))
      (node (ref "X9") (pin "15") (pinfunction "15_15") (pintype "power_in"))
    )
    (net (code "42") (name "Net-(C25-Pad1)") (class "Default")
      (node (ref "C25") (pin "1") (pinfunction "1_1") (pintype "passive"))
      (node (ref "L3") (pin "1") (pinfunction "1_1") (pintype "passive"))
      (node (ref "X9") (pin "16") (pinfunction "16_16") (pintype "power_in"))
    )
    (net (code "43") (name "Net-(DD1A-CBOT)") (class "Default")
      (node (ref "C26") (pin "2") (pinfunction "2_2") (pintype "passive"))
      (node (ref "DD1") (pin "37") (pinfunction "CBOT_37") (pintype "passive"))
    )
    (net (code "44") (name "Net-(DD1A-CTOP)") (class "Default")
      (node (ref "C26") (pin "1") (pinfunction "1_1") (pintype "passive"))
      (node (ref "DD1") (pin "40") (pinfunction "CTOP_40") (pintype "passive"))
    )
    (net (code "45") (name "Net-(DD1A-DEV_OFF_N)") (class "Default")
      (node (ref "DD1") (pin "28") (pinfunction "DEV_OFF_N_28") (pintype "input"))
      (node (ref "R22") (pin "1") (pinfunction "1_1") (pintype "passive"))
    )
    (net (code "46") (name "Net-(DD1A-JTAG_CLK)") (class "Default")
      (node (ref "DD1") (pin "19") (pinfunction "JTAG_CLK_19") (pintype "input"))
      (node (ref "R39") (pin "1") (pinfunction "1_1") (pintype "passive"))
      (node (ref "X10") (pin "1") (pinfunction "1_1") (pintype "passive"))
    )
    (net (code "47") (name "Net-(DD1A-JTAG_TDI)") (class "Default")
      (node (ref "DD1") (pin "29") (pinfunction "JTAG_TDI_29") (pintype "input"))
      (node (ref "R36") (pin "1") (pinfunction "1_1") (pintype "passive"))
      (node (ref "X10") (pin "4") (pinfunction "4_4") (pintype "passive"))
    )
    (net (code "48") (name "Net-(DD1A-JTAG_TDO)") (class "Default")
      (node (ref "DD1") (pin "4") (pinfunction "JTAG_TDO_4") (pintype "output"))
      (node (ref "R37") (pin "1") (pinfunction "1_1") (pintype "passive"))
      (node (ref "X10") (pin "3") (pinfunction "3_3") (pintype "passive"))
    )
    (net (code "49") (name "Net-(DD1A-JTAG_TMS)") (class "Default")
      (node (ref "DD1") (pin "18") (pinfunction "JTAG_TMS_18") (pintype "input"))
      (node (ref "R38") (pin "1") (pinfunction "1_1") (pintype "passive"))
      (node (ref "X10") (pin "2") (pinfunction "2_2") (pintype "passive"))
    )
    (net (code "50") (name "Net-(DD1A-LAN_PW_R_GOOD)") (class "Default")
      (node (ref "DD1") (pin "1") (pinfunction "LAN_PW_R_GOOD_1") (pintype "passive"))
      (node (ref "R21") (pin "2") (pinfunction "2_2") (pintype "passive"))
    )
    (net (code "51") (name "Net-(DD1A-LED0)") (class "Default")
      (node (ref "DD1") (pin "31") (pinfunction "LED0_31") (pintype "output"))
      (node (ref "R41") (pin "1") (pinfunction "1_1") (pintype "passive"))
    )
    (net (code "52") (name "Net-(DD1A-LED1)") (class "Default")
      (node (ref "DD1") (pin "30") (pinfunction "LED1_30") (pintype "output"))
      (node (ref "R43") (pin "1") (pinfunction "1_1") (pintype "passive"))
    )
    (net (code "53") (name "Net-(DD1A-LED2)") (class "Default")
      (node (ref "DD1") (pin "33") (pinfunction "LED2_33") (pintype "output"))
      (node (ref "R44") (pin "1") (pinfunction "1_1") (pintype "passive"))
    )
    (net (code "54") (name "Net-(DD1A-NC_SI_CLK_IN)") (class "Default")
      (node (ref "DD1") (pin "2") (pinfunction "NC_SI_CLK_IN_2") (pintype "input"))
      (node (ref "R23") (pin "2") (pinfunction "2_2") (pintype "passive"))
    )
    (net (code "55") (name "Net-(DD1A-NC_SI_CRS_DV)") (class "Default")
      (node (ref "DD1") (pin "3") (pinfunction "NC_SI_CRS_DV_3") (pintype "output"))
      (node (ref "R25") (pin "2") (pinfunction "2_2") (pintype "passive"))
    )
    (net (code "56") (name "Net-(DD1A-NC_SI_RXD0)") (class "Default")
      (node (ref "DD1") (pin "6") (pinfunction "NC_SI_RXD0_6") (pintype "output"))
      (node (ref "R26") (pin "2") (pinfunction "2_2") (pintype "passive"))
    )
    (net (code "57") (name "Net-(DD1A-NC_SI_RX_D1)") (class "Default")
      (node (ref "DD1") (pin "5") (pinfunction "NC_SI_RX_D1_5") (pintype "output"))
      (node (ref "R28") (pin "2") (pinfunction "2_2") (pintype "passive"))
    )
    (net (code "58") (name "Net-(DD1A-NC_SI_TXD0)") (class "Default")
      (node (ref "DD1") (pin "9") (pinfunction "NC_SI_TXD0_9") (pintype "input"))
      (node (ref "R30") (pin "2") (pinfunction "2_2") (pintype "passive"))
    )
    (net (code "59") (name "Net-(DD1A-NC_SI_TXD1)") (class "Default")
      (node (ref "DD1") (pin "8") (pinfunction "NC_SI_TXD1_8") (pintype "input"))
      (node (ref "R32") (pin "2") (pinfunction "2_2") (pintype "passive"))
    )
    (net (code "60") (name "Net-(DD1A-NC_SI_TX_EN)") (class "Default")
      (node (ref "DD1") (pin "7") (pinfunction "NC_SI_TX_EN_7") (pintype "input"))
      (node (ref "R29") (pin "2") (pinfunction "2_2") (pintype "passive"))
    )
    (net (code "61") (name "Net-(DD1A-NVM_CS_N)") (class "Default")
      (node (ref "DD1") (pin "15") (pinfunction "NVM_CS_N_15") (pintype "output"))
      (node (ref "R40") (pin "2") (pinfunction "2_2") (pintype "passive"))
    )
    (net (code "62") (name "Net-(DD1A-NVM_SI)") (class "Default")
      (node (ref "DD1") (pin "12") (pinfunction "NVM_SI_12") (pintype "output"))
      (node (ref "R33") (pin "2") (pinfunction "2_2") (pintype "passive"))
    )
    (net (code "63") (name "Net-(DD1A-NVM_SK)") (class "Default")
      (node (ref "DD1") (pin "13") (pinfunction "NVM_SK_13") (pintype "output"))
      (node (ref "R35") (pin "2") (pinfunction "2_2") (pintype "passive"))
    )
    (net (code "64") (name "Net-(DD1A-NVM_SO)") (class "Default")
      (node (ref "DD1") (pin "14") (pinfunction "NVM_SO_14") (pintype "input"))
      (node (ref "R34") (pin "2") (pinfunction "2_2") (pintype "passive"))
    )
    (net (code "65") (name "Net-(DD1A-RSET)") (class "Default")
      (node (ref "DD1") (pin "48") (pinfunction "RSET_48") (pintype "passive"))
      (node (ref "R54") (pin "2") (pinfunction "2_2") (pintype "passive"))
    )
    (net (code "66") (name "Net-(DD1A-SMB_ALRT)") (class "Default")
      (node (ref "DD1") (pin "35") (pinfunction "SMB_ALRT_35") (pintype "output"))
      (node (ref "R51") (pin "2") (pinfunction "2_2") (pintype "passive"))
    )
    (net (code "67") (name "Net-(DD1A-SMB_CLK)") (class "Default")
      (node (ref "DD1") (pin "34") (pinfunction "SMB_CLK_34") (pintype "bidirectional"))
      (node (ref "R52") (pin "2") (pinfunction "2_2") (pintype "passive"))
    )
    (net (code "68") (name "Net-(DD1A-SMB_DATA)") (class "Default")
      (node (ref "DD1") (pin "36") (pinfunction "SMB_DATA_36") (pintype "bidirectional"))
      (node (ref "R53") (pin "2") (pinfunction "2_2") (pintype "passive"))
    )
    (net (code "69") (name "Net-(DD1A-XTAL1)") (class "Default")
      (node (ref "C21") (pin "1") (pinfunction "1_1") (pintype "passive"))
      (node (ref "DD1") (pin "46") (pinfunction "XTAL1_46") (pintype "input"))
      (node (ref "ZQ2") (pin "1") (pinfunction "1_1") (pintype "passive"))
    )
    (net (code "70") (name "Net-(DD1A-XTAL2)") (class "Default")
      (node (ref "C22") (pin "1") (pinfunction "1_1") (pintype "passive"))
      (node (ref "DD1") (pin "45") (pinfunction "XTAL2_45") (pintype "output"))
      (node (ref "ZQ2") (pin "3") (pinfunction "3_3") (pintype "passive"))
    )
    (net (code "71") (name "Net-(DD1B-VDD1p5-Pad56)") (class "Default")
      (node (ref "DD1") (pin "56") (pinfunction "VDD1p5_56") (pintype "passive"))
      (node (ref "R62") (pin "2") (pinfunction "2_2") (pintype "passive"))
    )
    (net (code "72") (name "Net-(DD1B-VDD3p3-Pad51)") (class "Default")
      (node (ref "DD1") (pin "51") (pinfunction "VDD3p3_51") (pintype "passive"))
      (node (ref "R63") (pin "2") (pinfunction "2_2") (pintype "passive"))
      (node (ref "R64") (pin "2") (pinfunction "2_2") (pintype "passive"))
    )
    (net (code "73") (name "Net-(DD2-~{RESET}{slash}IO3)") (class "Default")
      (node (ref "DD2") (pin "7") (pinfunction "~{RESET}/IO3_7") (pintype "input"))
      (node (ref "R60") (pin "1") (pinfunction "1_1") (pintype "passive"))
    )
    (net (code "74") (name "Net-(DD2-~{WP}{slash}IO2)") (class "Default")
      (node (ref "DD2") (pin "3") (pinfunction "~{WP}/IO2_3") (pintype "input"))
      (node (ref "R61") (pin "2") (pinfunction "2_2") (pintype "passive"))
      (node (ref "X11") (pin "2") (pinfunction "2_2") (pintype "passive"))
    )
    (net (code "75") (name "Net-(HL3-A)") (class "Default")
      (node (ref "HL3") (pin "1") (pinfunction "A_1") (pintype "power_in"))
      (node (ref "R42") (pin "1") (pinfunction "1_1") (pintype "passive"))
    )
    (net (code "76") (name "Net-(HL3-K)") (class "Default")
      (node (ref "HL3") (pin "2") (pinfunction "K_2") (pintype "power_in"))
      (node (ref "R43") (pin "2") (pinfunction "2_2") (pintype "passive"))
    )
    (net (code "77") (name "Net-(HL4-A)") (class "Default")
      (node (ref "HL4") (pin "1") (pinfunction "A_1") (pintype "power_in"))
      (node (ref "HL5") (pin "2") (pinfunction "K_2") (pintype "power_in"))
      (node (ref "R44") (pin "2") (pinfunction "2_2") (pintype "passive"))
    )
    (net (code "78") (name "Net-(HL4-K)") (class "Default")
      (node (ref "HL4") (pin "2") (pinfunction "K_2") (pintype "power_in"))
      (node (ref "HL5") (pin "1") (pinfunction "A_1") (pintype "power_in"))
      (node (ref "R41") (pin "2") (pinfunction "2_2") (pintype "passive"))
    )
    (net (code "79") (name "Net-(R24-Pad1)") (class "Default")
      (node (ref "R24") (pin "1") (pinfunction "1_1") (pintype "passive"))
      (node (ref "X9") (pin "7") (pinfunction "7_7") (pintype "input"))
    )
    (net (code "80") (name "Net-(R27-Pad1)") (class "Default")
      (node (ref "R27") (pin "1") (pinfunction "1_1") (pintype "passive"))
      (node (ref "X9") (pin "9") (pinfunction "9_9") (pintype "input"))
    )
    (net (code "81") (name "Net-(R55-Pad1)") (class "Default")
      (node (ref "R55") (pin "1") (pinfunction "1_1") (pintype "passive"))
      (node (ref "X11") (pin "1") (pinfunction "1_1") (pintype "passive"))
    )
    (net (code "82") (name "Net-(VT3-S)") (class "Default")
      (node (ref "R50") (pin "1") (pinfunction "1_1") (pintype "passive"))
      (node (ref "VT3") (pin "2") (pinfunction "S_2") (pintype "passive"))
    )
    (net (code "83") (name "unconnected-(DD1A-MDI_PLUS0-Pad58)") (class "Default")
      (node (ref "DD1") (pin "58") (pinfunction "MDI_PLUS0_58") (pintype "bidirectional+no_connect"))
    )
    (net (code "84") (name "unconnected-(DD1A-NC-Pad22)") (class "Default")
      (node (ref "DD1") (pin "22") (pinfunction "NC_22") (pintype "passive+no_connect"))
    )
    (net (code "85") (name "unconnected-(DD1A-NC_SI_ARB_IN-Pad43)") (class "Default")
      (node (ref "DD1") (pin "43") (pinfunction "NC_SI_ARB_IN_43") (pintype "input+no_connect"))
    )
    (net (code "86") (name "unconnected-(DD1A-NC_SI_ARB_OUT-Pad44)") (class "Default")
      (node (ref "DD1") (pin "44") (pinfunction "NC_SI_ARB_OUT_44") (pintype "output+no_connect"))
    )
  )
)
